# esp32-acv-v10.net
KiCad netlist of a schematic drawn in EAGLE
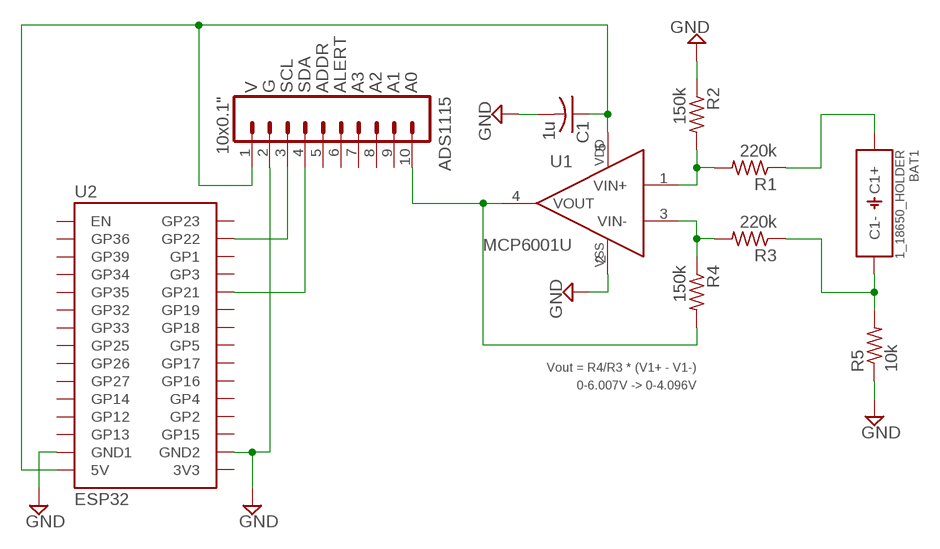
[diagram p0: schematic, sheet 1]

(export (version "E")
  (design (tool "Eeschema 10.0.6"))
  (components
    (comp (ref "ADS1115")
      (value "10x0.1\"")
      (footprint "eagle-import:1X10")
      (libsource (lib "eagle-import") (part "M10{dblquote}"))
    )
    (comp (ref "BAT1")
      (value "1_18650_HOLDER")
      (footprint "eagle-import:1S_18650_SMD_NH")
      (libsource (lib "eagle-import") (part "1_18650_HOLDER"))
    )
    (comp (ref "C1")
      (value "1u")
      (footprint "eagle-import:C0402")
      (libsource (lib "eagle-import") (part "C-USC0402"))
    )
    (comp (ref "R1")
      (value "220k")
      (footprint "eagle-import:R0402")
      (libsource (lib "eagle-import") (part "R-US_R0402"))
    )
    (comp (ref "R2")
      (value "150k")
      (footprint "eagle-import:R0402")
      (libsource (lib "eagle-import") (part "R-US_R0402"))
    )
    (comp (ref "R3")
      (value "220k")
      (footprint "eagle-import:R0402")
      (libsource (lib "eagle-import") (part "R-US_R0402"))
    )
    (comp (ref "R4")
      (value "150k")
      (footprint "eagle-import:R0402")
      (libsource (lib "eagle-import") (part "R-US_R0402"))
    )
    (comp (ref "R5")
      (value "10k")
      (footprint "eagle-import:R0402")
      (libsource (lib "eagle-import") (part "R-US_R0402"))
    )
    (comp (ref "U1")
      (value "MCP6001U")
      (footprint "eagle-import:SOT23-5")
      (libsource (lib "eagle-import") (part "MCP6001U"))
    )
    (comp (ref "U2")
      (value "ESP32")
      (footprint "eagle-import:ESP32-30P")
      (libsource (lib "eagle-import") (part "ESP32"))
    )
  )
  (nets
    (net (code "1") (name "GND") (class "Default")
      (node (ref "ADS1115") (pin "2") (pinfunction "2_2") (pintype "passive"))
      (node (ref "C1") (pin "2") (pinfunction "2_2") (pintype "passive"))
      (node (ref "R2") (pin "1") (pinfunction "1_1") (pintype "passive"))
      (node (ref "R5") (pin "1") (pinfunction "1_1") (pintype "passive"))
      (node (ref "U1") (pin "2") (pinfunction "VSS_2") (pintype "bidirectional"))
      (node (ref "U2") (pin "2") (pinfunction "GND2_2") (pintype "bidirectional"))
      (node (ref "U2") (pin "29") (pinfunction "GND1_29") (pintype "bidirectional"))
    )
    (net (code "2") (name "Net-(BAT1-C1+)") (class "Default")
      (node (ref "BAT1") (pin "1+") (pinfunction "C1+_1+") (pintype "bidirectional"))
      (node (ref "R1") (pin "1") (pinfunction "1_1") (pintype "passive"))
    )
    (net (code "3") (name "Net-(BAT1-C1-)") (class "Default")
      (node (ref "BAT1") (pin "1-") (pinfunction "C1-_1-") (pintype "bidirectional"))
      (node (ref "R3") (pin "1") (pinfunction "1_1") (pintype "passive"))
      (node (ref "R5") (pin "2") (pinfunction "2_2") (pintype "passive"))
    )
    (net (code "4") (name "Net-(U1-VDD)") (class "Default")
      (node (ref "ADS1115") (pin "1") (pinfunction "1_1") (pintype "passive"))
      (node (ref "C1") (pin "1") (pinfunction "1_1") (pintype "passive"))
      (node (ref "U1") (pin "5") (pinfunction "VDD_5") (pintype "bidirectional"))
      (node (ref "U2") (pin "30") (pinfunction "5V_30") (pintype "bidirectional"))
    )
    (net (code "5") (name "Net-(U1-VIN+)") (class "Default")
      (node (ref "R1") (pin "2") (pinfunction "2_2") (pintype "passive"))
      (node (ref "R2") (pin "2") (pinfunction "2_2") (pintype "passive"))
      (node (ref "U1") (pin "1") (pinfunction "VIN+_1") (pintype "bidirectional"))
    )
    (net (code "6") (name "Net-(U1-VIN-)") (class "Default")
      (node (ref "R3") (pin "2") (pinfunction "2_2") (pintype "passive"))
      (node (ref "R4") (pin "1") (pinfunction "1_1") (pintype "passive"))
      (node (ref "U1") (pin "3") (pinfunction "VIN-_3") (pintype "bidirectional"))
    )
    (net (code "7") (name "Net-(U1-VOUT)") (class "Default")
      (node (ref "ADS1115") (pin "10") (pinfunction "10_10") (pintype "passive"))
      (node (ref "R4") (pin "2") (pinfunction "2_2") (pintype "passive"))
      (node (ref "U1") (pin "4") (pinfunction "VOUT_4") (pintype "bidirectional"))
    )
    (net (code "8") (name "Net-(U2-GP21)") (class "Default")
      (node (ref "ADS1115") (pin "4") (pinfunction "4_4") (pintype "passive"))
      (node (ref "U2") (pin "11") (pinfunction "GP21_11") (pintype "bidirectional"))
    )
    (net (code "9") (name "Net-(U2-GP22)") (class "Default")
      (node (ref "ADS1115") (pin "3") (pinfunction "3_3") (pintype "passive"))
      (node (ref "U2") (pin "14") (pinfunction "GP22_14") (pintype "bidirectional"))
    )
    (net (code "10") (name "unconnected-(ADS1115-Pad5)") (class "Default")
      (node (ref "ADS1115") (pin "5") (pinfunction "5_5") (pintype "passive"))
    )
    (net (code "11") (name "unconnected-(ADS1115-Pad6)") (class "Default")
      (node (ref "ADS1115") (pin "6") (pinfunction "6_6") (pintype "passive"))
    )
    (net (code "12") (name "unconnected-(ADS1115-Pad7)") (class "Default")
      (node (ref "ADS1115") (pin "7") (pinfunction "7_7") (pintype "passive"))
    )
    (net (code "13") (name "unconnected-(ADS1115-Pad8)") (class "Default")
      (node (ref "ADS1115") (pin "8") (pinfunction "8_8") (pintype "passive"))
    )
    (net (code "14") (name "unconnected-(ADS1115-Pad9)") (class "Default")
      (node (ref "ADS1115") (pin "9") (pinfunction "9_9") (pintype "passive"))
    )
    (net (code "15") (name "unconnected-(U2-3V3-Pad1)") (class "Default")
      (node (ref "U2") (pin "1") (pinfunction "3V3_1") (pintype "bidirectional"))
    )
    (net (code "16") (name "unconnected-(U2-EN-Pad16)") (class "Default")
      (node (ref "U2") (pin "16") (pinfunction "EN_16") (pintype "bidirectional"))
    )
    (net (code "17") (name "unconnected-(U2-GP1-Pad13)") (class "Default")
      (node (ref "U2") (pin "13") (pinfunction "GP1_13") (pintype "bidirectional"))
    )
    (net (code "18") (name "unconnected-(U2-GP2-Pad4)") (class "Default")
      (node (ref "U2") (pin "4") (pinfunction "GP2_4") (pintype "bidirectional"))
    )
    (net (code "19") (name "unconnected-(U2-GP3-Pad12)") (class "Default")
      (node (ref "U2") (pin "12") (pinfunction "GP3_12") (pintype "bidirectional"))
    )
    (net (code "20") (name "unconnected-(U2-GP4-Pad5)") (class "Default")
      (node (ref "U2") (pin "5") (pinfunction "GP4_5") (pintype "bidirectional"))
    )
    (net (code "21") (name "unconnected-(U2-GP5-Pad8)") (class "Default")
      (node (ref "U2") (pin "8") (pinfunction "GP5_8") (pintype "bidirectional"))
    )
    (net (code "22") (name "unconnected-(U2-GP12-Pad27)") (class "Default")
      (node (ref "U2") (pin "27") (pinfunction "GP12_27") (pintype "bidirectional"))
    )
    (net (code "23") (name "unconnected-(U2-GP13-Pad28)") (class "Default")
      (node (ref "U2") (pin "28") (pinfunction "GP13_28") (pintype "bidirectional"))
    )
    (net (code "24") (name "unconnected-(U2-GP14-Pad26)") (class "Default")
      (node (ref "U2") (pin "26") (pinfunction "GP14_26") (pintype "bidirectional"))
    )
    (net (code "25") (name "unconnected-(U2-GP15-Pad3)") (class "Default")
      (node (ref "U2") (pin "3") (pinfunction "GP15_3") (pintype "bidirectional"))
    )
    (net (code "26") (name "unconnected-(U2-GP16-Pad6)") (class "Default")
      (node (ref "U2") (pin "6") (pinfunction "GP16_6") (pintype "bidirectional"))
    )
    (net (code "27") (name "unconnected-(U2-GP17-Pad7)") (class "Default")
      (node (ref "U2") (pin "7") (pinfunction "GP17_7") (pintype "bidirectional"))
    )
    (net (code "28") (name "unconnected-(U2-GP18-Pad9)") (class "Default")
      (node (ref "U2") (pin "9") (pinfunction "GP18_9") (pintype "bidirectional"))
    )
    (net (code "29") (name "unconnected-(U2-GP19-Pad10)") (class "Default")
      (node (ref "U2") (pin "10") (pinfunction "GP19_10") (pintype "bidirectional"))
    )
    (net (code "30") (name "unconnected-(U2-GP23-Pad15)") (class "Default")
      (node (ref "U2") (pin "15") (pinfunction "GP23_15") (pintype "bidirectional"))
    )
    (net (code "31") (name "unconnected-(U2-GP25-Pad23)") (class "Default")
      (node (ref "U2") (pin "23") (pinfunction "GP25_23") (pintype "bidirectional"))
    )
    (net (code "32") (name "unconnected-(U2-GP26-Pad24)") (class "Default")
      (node (ref "U2") (pin "24") (pinfunction "GP26_24") (pintype "bidirectional"))
    )
    (net (code "33") (name "unconnected-(U2-GP27-Pad25)") (class "Default")
      (node (ref "U2") (pin "25") (pinfunction "GP27_25") (pintype "bidirectional"))
    )
    (net (code "34") (name "unconnected-(U2-GP32-Pad21)") (class "Default")
      (node (ref "U2") (pin "21") (pinfunction "GP32_21") (pintype "bidirectional"))
    )
    (net (code "35") (name "unconnected-(U2-GP33-Pad22)") (class "Default")
      (node (ref "U2") (pin "22") (pinfunction "GP33_22") (pintype "bidirectional"))
    )
    (net (code "36") (name "unconnected-(U2-GP34-Pad19)") (class "Default")
      (node (ref "U2") (pin "19") (pinfunction "GP34_19") (pintype "bidirectional"))
    )
    (net (code "37") (name "unconnected-(U2-GP35-Pad20)") (class "Default")
      (node (ref "U2") (pin "20") (pinfunction "GP35_20") (pintype "bidirectional"))
    )
    (net (code "38") (name "unconnected-(U2-GP36-Pad17)") (class "Default")
      (node (ref "U2") (pin "17") (pinfunction "GP36_17") (pintype "bidirectional"))
    )
    (net (code "39") (name "unconnected-(U2-GP39-Pad18)") (class "Default")
      (node (ref "U2") (pin "18") (pinfunction "GP39_18") (pintype "bidirectional"))
    )
  )
)
